# esp8266-proto-board-0805.net
KiCad netlist of a schematic drawn in EAGLE
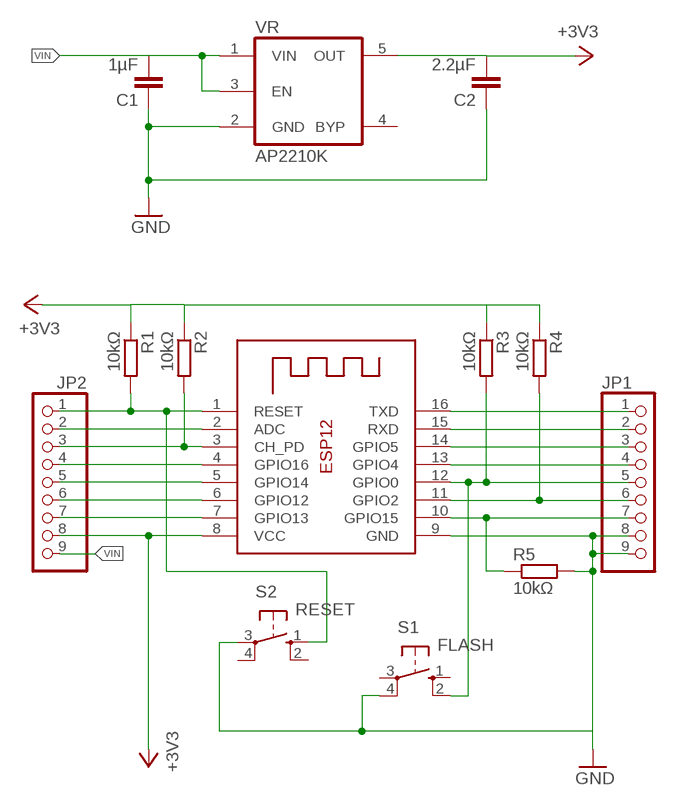
[diagram p0: schematic, sheet 1]

(export (version "E")
  (design (tool "Eeschema 10.0.6"))
  (components
    (comp (ref "C1")
      (value "1µF")
      (footprint "eagle-import:C0805K")
      (libsource (lib "eagle-import") (part "C-EUC0805K"))
    )
    (comp (ref "C2")
      (value "2.2µF")
      (footprint "eagle-import:C0805K")
      (libsource (lib "eagle-import") (part "C-EUC0805K"))
    )
    (comp (ref "JP1")
      (value "PINHD-1X9")
      (footprint "eagle-import:1X09-BIG")
      (libsource (lib "eagle-import") (part "PINHD-1X9"))
    )
    (comp (ref "JP2")
      (value "PINHD-1X9")
      (footprint "eagle-import:1X09-BIG")
      (libsource (lib "eagle-import") (part "PINHD-1X9"))
    )
    (comp (ref "R1")
      (value "10kΩ")
      (footprint "eagle-import:R0805W")
      (libsource (lib "eagle-import") (part "R-EU_R0805W"))
    )
    (comp (ref "R2")
      (value "10kΩ")
      (footprint "eagle-import:R0805W")
      (libsource (lib "eagle-import") (part "R-EU_R0805W"))
    )
    (comp (ref "R3")
      (value "10kΩ")
      (footprint "eagle-import:R0805W")
      (libsource (lib "eagle-import") (part "R-EU_R0805W"))
    )
    (comp (ref "R4")
      (value "10kΩ")
      (footprint "eagle-import:R0805W")
      (libsource (lib "eagle-import") (part "R-EU_R0805W"))
    )
    (comp (ref "R5")
      (value "10kΩ")
      (footprint "eagle-import:R0805W")
      (libsource (lib "eagle-import") (part "R-EU_R0805W"))
    )
    (comp (ref "S1")
      (value "FLASH")
      (footprint "eagle-import:B3F-10XX")
      (fields (field (name "MPN") "B3F-1000"))
      (libsource (lib "eagle-import") (part "10-XX"))
    )
    (comp (ref "S2")
      (value "RESET")
      (footprint "eagle-import:B3F-10XX")
      (fields (field (name "MPN") "B3F-1000"))
      (libsource (lib "eagle-import") (part "10-XX"))
    )
    (comp (ref "U1")
      (value "ESP-12")
      (footprint "eagle-import:ESP-12")
      (libsource (lib "eagle-import") (part "ESP-12"))
    )
    (comp (ref "VR")
      (value "AP2210K")
      (footprint "eagle-import:SOT23-5")
      (libsource (lib "eagle-import") (part "AP2210K"))
    )
  )
  (nets
    (net (code "1") (name "+3V3") (class "Default")
      (node (ref "C2") (pin "2") (pinfunction "2_2") (pintype "passive"))
      (node (ref "JP2") (pin "8") (pinfunction "8_8") (pintype "passive"))
      (node (ref "R1") (pin "1") (pinfunction "1_1") (pintype "passive"))
      (node (ref "R2") (pin "1") (pinfunction "1_1") (pintype "passive"))
      (node (ref "R3") (pin "1") (pinfunction "1_1") (pintype "passive"))
      (node (ref "R4") (pin "1") (pinfunction "1_1") (pintype "passive"))
      (node (ref "U1") (pin "8") (pinfunction "VCC_8") (pintype "power_in"))
      (node (ref "VR") (pin "5") (pinfunction "OUT_5") (pintype "power_in"))
    )
    (net (code "2") (name "GND") (class "Default")
      (node (ref "C1") (pin "1") (pinfunction "1_1") (pintype "passive"))
      (node (ref "C2") (pin "1") (pinfunction "1_1") (pintype "passive"))
      (node (ref "JP1") (pin "8") (pinfunction "8_8") (pintype "passive"))
      (node (ref "JP1") (pin "9") (pinfunction "9_9") (pintype "passive"))
      (node (ref "R5") (pin "2") (pinfunction "2_2") (pintype "passive"))
      (node (ref "S1") (pin "4") (pinfunction "P1_4") (pintype "passive"))
      (node (ref "S2") (pin "3") (pinfunction "P_3") (pintype "passive"))
      (node (ref "U1") (pin "9") (pinfunction "GND_9") (pintype "power_in"))
      (node (ref "VR") (pin "2") (pinfunction "GND_2") (pintype "power_in"))
    )
    (net (code "3") (name "Net-(S1-S1)") (class "Default")
      (node (ref "JP1") (pin "5") (pinfunction "5_5") (pintype "passive"))
      (node (ref "R3") (pin "2") (pinfunction "2_2") (pintype "passive"))
      (node (ref "S1") (pin "2") (pinfunction "S1_2") (pintype "passive"))
      (node (ref "U1") (pin "12") (pinfunction "GPIO0_12") (pintype "bidirectional"))
    )
    (net (code "4") (name "Net-(S2-S)") (class "Default")
      (node (ref "JP2") (pin "1") (pinfunction "1_1") (pintype "passive"))
      (node (ref "R1") (pin "2") (pinfunction "2_2") (pintype "passive"))
      (node (ref "S2") (pin "1") (pinfunction "S_1") (pintype "passive"))
      (node (ref "U1") (pin "1") (pinfunction "RESET_1") (pintype "input"))
    )
    (net (code "5") (name "Net-(U1-ADC)") (class "Default")
      (node (ref "JP2") (pin "2") (pinfunction "2_2") (pintype "passive"))
      (node (ref "U1") (pin "2") (pinfunction "ADC_2") (pintype "passive"))
    )
    (net (code "6") (name "Net-(U1-CH_PD)") (class "Default")
      (node (ref "JP2") (pin "3") (pinfunction "3_3") (pintype "passive"))
      (node (ref "R2") (pin "2") (pinfunction "2_2") (pintype "passive"))
      (node (ref "U1") (pin "3") (pinfunction "CH_PD_3") (pintype "input"))
    )
    (net (code "7") (name "Net-(U1-GPIO2)") (class "Default")
      (node (ref "JP1") (pin "6") (pinfunction "6_6") (pintype "passive"))
      (node (ref "R4") (pin "2") (pinfunction "2_2") (pintype "passive"))
      (node (ref "U1") (pin "11") (pinfunction "GPIO2_11") (pintype "bidirectional"))
    )
    (net (code "8") (name "Net-(U1-GPIO4)") (class "Default")
      (node (ref "JP1") (pin "4") (pinfunction "4_4") (pintype "passive"))
      (node (ref "U1") (pin "13") (pinfunction "GPIO4_13") (pintype "bidirectional"))
    )
    (net (code "9") (name "Net-(U1-GPIO5)") (class "Default")
      (node (ref "JP1") (pin "3") (pinfunction "3_3") (pintype "passive"))
      (node (ref "U1") (pin "14") (pinfunction "GPIO5_14") (pintype "bidirectional"))
    )
    (net (code "10") (name "Net-(U1-GPIO12)") (class "Default")
      (node (ref "JP2") (pin "6") (pinfunction "6_6") (pintype "passive"))
      (node (ref "U1") (pin "6") (pinfunction "GPIO12_6") (pintype "bidirectional"))
    )
    (net (code "11") (name "Net-(U1-GPIO13)") (class "Default")
      (node (ref "JP2") (pin "7") (pinfunction "7_7") (pintype "passive"))
      (node (ref "U1") (pin "7") (pinfunction "GPIO13_7") (pintype "bidirectional"))
    )
    (net (code "12") (name "Net-(U1-GPIO14)") (class "Default")
      (node (ref "JP2") (pin "5") (pinfunction "5_5") (pintype "passive"))
      (node (ref "U1") (pin "5") (pinfunction "GPIO14_5") (pintype "bidirectional"))
    )
    (net (code "13") (name "Net-(U1-GPIO15)") (class "Default")
      (node (ref "JP1") (pin "7") (pinfunction "7_7") (pintype "passive"))
      (node (ref "R5") (pin "1") (pinfunction "1_1") (pintype "passive"))
      (node (ref "U1") (pin "10") (pinfunction "GPIO15_10") (pintype "bidirectional"))
    )
    (net (code "14") (name "Net-(U1-GPIO16)") (class "Default")
      (node (ref "JP2") (pin "4") (pinfunction "4_4") (pintype "passive"))
      (node (ref "U1") (pin "4") (pinfunction "GPIO16_4") (pintype "bidirectional"))
    )
    (net (code "15") (name "Net-(U1-RXD)") (class "Default")
      (node (ref "JP1") (pin "2") (pinfunction "2_2") (pintype "passive"))
      (node (ref "U1") (pin "15") (pinfunction "RXD_15") (pintype "input"))
    )
    (net (code "16") (name "Net-(U1-TXD)") (class "Default")
      (node (ref "JP1") (pin "1") (pinfunction "1_1") (pintype "passive"))
      (node (ref "U1") (pin "16") (pinfunction "TXD_16") (pintype "output"))
    )
    (net (code "17") (name "VIN") (class "Default")
      (node (ref "C1") (pin "2") (pinfunction "2_2") (pintype "passive"))
      (node (ref "JP2") (pin "9") (pinfunction "9_9") (pintype "passive"))
      (node (ref "VR") (pin "1") (pinfunction "VIN_1") (pintype "input"))
      (node (ref "VR") (pin "3") (pinfunction "EN_3") (pintype "input"))
    )
    (net (code "18") (name "unconnected-(S1-P-Pad3)") (class "Default")
      (node (ref "S1") (pin "3") (pinfunction "P_3") (pintype "passive"))
    )
    (net (code "19") (name "unconnected-(S1-S-Pad1)") (class "Default")
      (node (ref "S1") (pin "1") (pinfunction "S_1") (pintype "passive"))
    )
    (net (code "20") (name "unconnected-(S2-P1-Pad4)") (class "Default")
      (node (ref "S2") (pin "4") (pinfunction "P1_4") (pintype "passive"))
    )
    (net (code "21") (name "unconnected-(S2-S1-Pad2)") (class "Default")
      (node (ref "S2") (pin "2") (pinfunction "S1_2") (pintype "passive"))
    )
    (net (code "22") (name "unconnected-(VR-BYP-Pad4)") (class "Default")
      (node (ref "VR") (pin "4") (pinfunction "BYP_4") (pintype "output"))
    )
  )
)
